# PressureSensorCircuit.net
KiCad netlist of a schematic drawn in Altium Designer
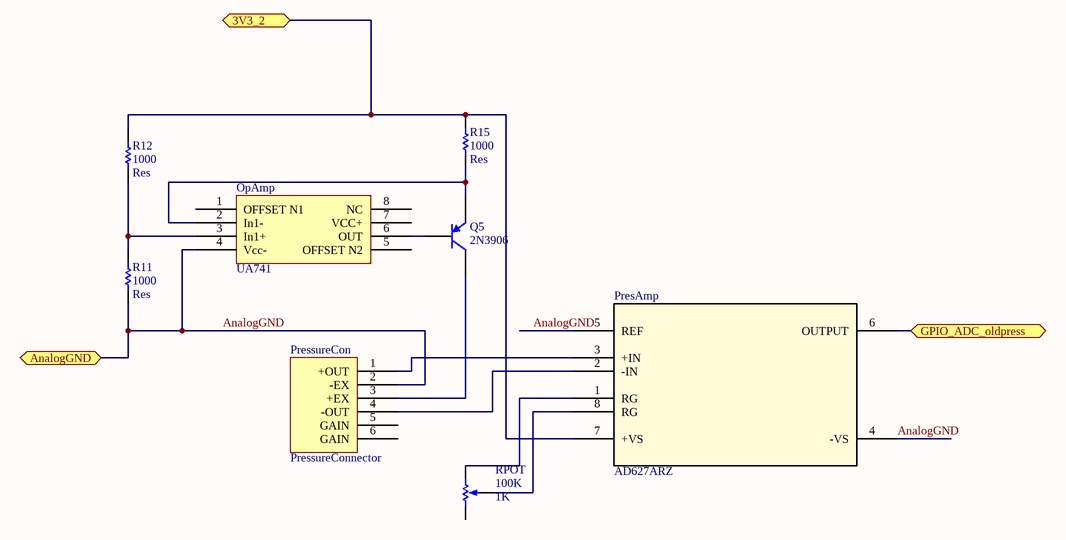
[diagram p0: PressureSensorCircuit.SchDoc]

(export (version "E")
  (design (tool "Eeschema 10.0.6"))
  (components
    (comp (ref "OpAmp")
      (value "UA741")
      (footprint "UmbilicalConnectors:UA741")
      (libsource (lib "UmbilicalBoardV2") (part "UA741"))
    )
    (comp (ref "PresAmp")
      (value "AD627ARZ")
      (footprint "R_8")
      (description "Imported")
      (libsource (lib "2016-04-06_02-20-10") (part "AD627ARZ"))
    )
    (comp (ref "PressureCon")
      (value "PressureConnector")
      (footprint "UmbilicalConnectors:Pressure Connector")
      (description "Molex 53261-0671")
      (libsource (lib "UmbilicalBoardV2") (part "PressureConnector"))
    )
    (comp (ref "Q5")
      (value "2N3906")
      (footprint "TO-92A")
      (description "PNP General Purpose Amplifier")
      (fields (field (name "PUBLISHER") "Altium Limited"))
      (libsource (lib "Miscellaneous Devices") (part "2N3906"))
    )
    (comp (ref "R11")
      (value "1000")
      (footprint "AXIAL-0.3")
      (description "Resistor- 696-1552-ND")
      (fields (field (name "ALTIUM_VALUE") "Res") (field (name "PUBLISHER") "Altium Limited"))
      (libsource (lib "Miscellaneous Devices") (part "Res1"))
    )
    (comp (ref "R12")
      (value "1000")
      (footprint "AXIAL-0.3")
      (description "Resistor- 696-1552-ND")
      (fields (field (name "ALTIUM_VALUE") "Res") (field (name "PUBLISHER") "Altium Limited"))
      (libsource (lib "Miscellaneous Devices") (part "Res1"))
    )
    (comp (ref "R15")
      (value "1000")
      (footprint "AXIAL-0.3")
      (description "Resistor- 696-1552-ND")
      (fields (field (name "ALTIUM_VALUE") "Res") (field (name "PUBLISHER") "Altium Limited"))
      (libsource (lib "Miscellaneous Devices") (part "Res1"))
    )
    (comp (ref "RPOT")
      (value "100K")
      (footprint "VR5")
      (description "Potentiometer")
      (fields (field (name "ALTIUM_VALUE") "1K") (field (name "PUBLISHER") "Altium Limited"))
      (libsource (lib "Miscellaneous Devices") (part "RPot"))
    )
  )
  (nets
    (net (code "1") (name "/3V3_2") (class "Default")
      (node (ref "PresAmp") (pin "7") (pinfunction "+VS_7") (pintype "passive"))
      (node (ref "R12") (pin "1") (pinfunction "1_1") (pintype "passive"))
      (node (ref "R15") (pin "1") (pinfunction "1_1") (pintype "passive"))
    )
    (net (code "2") (name "/AnalogGND") (class "Default")
      (node (ref "OpAmp") (pin "4") (pinfunction "Vcc-_4") (pintype "passive"))
      (node (ref "PresAmp") (pin "4") (pinfunction "-VS_4") (pintype "passive"))
      (node (ref "PresAmp") (pin "5") (pinfunction "REF_5") (pintype "passive"))
      (node (ref "PressureCon") (pin "2") (pinfunction "-EX_2") (pintype "passive"))
      (node (ref "R11") (pin "2") (pinfunction "2_2") (pintype "passive"))
    )
    (net (code "3") (name "/GPIO_ADC_oldpress") (class "Default")
      (node (ref "PresAmp") (pin "6") (pinfunction "OUTPUT_6") (pintype "passive"))
    )
    (net (code "4") (name "Net-(OpAmp-In1+)") (class "Default")
      (node (ref "OpAmp") (pin "3") (pinfunction "In1+_3") (pintype "passive"))
      (node (ref "R11") (pin "1") (pinfunction "1_1") (pintype "passive"))
      (node (ref "R12") (pin "2") (pinfunction "2_2") (pintype "passive"))
    )
    (net (code "5") (name "Net-(OpAmp-In1-)") (class "Default")
      (node (ref "OpAmp") (pin "2") (pinfunction "In1-_2") (pintype "passive"))
      (node (ref "Q5") (pin "1") (pinfunction "E_1") (pintype "passive"))
      (node (ref "R15") (pin "2") (pinfunction "2_2") (pintype "passive"))
    )
    (net (code "6") (name "Net-(OpAmp-OUT)") (class "Default")
      (node (ref "OpAmp") (pin "6") (pinfunction "OUT_6") (pintype "passive"))
      (node (ref "Q5") (pin "2") (pinfunction "B_2") (pintype "passive"))
    )
    (net (code "7") (name "Net-(PresAmp-+IN)") (class "Default")
      (node (ref "PresAmp") (pin "3") (pinfunction "+IN_3") (pintype "passive"))
      (node (ref "PressureCon") (pin "1") (pinfunction "+OUT_1") (pintype "passive"))
    )
    (net (code "8") (name "Net-(PresAmp--IN)") (class "Default")
      (node (ref "PresAmp") (pin "2") (pinfunction "-IN_2") (pintype "passive"))
      (node (ref "PressureCon") (pin "4") (pinfunction "-OUT_4") (pintype "passive"))
    )
    (net (code "9") (name "Net-(PressureCon-+EX)") (class "Default")
      (node (ref "PressureCon") (pin "3") (pinfunction "+EX_3") (pintype "passive"))
      (node (ref "Q5") (pin "3") (pinfunction "C_3") (pintype "passive"))
    )
    (net (code "10") (name "Net-(RPOT-BOT)") (class "Default")
      (node (ref "PresAmp") (pin "1") (pinfunction "RG_1") (pintype "passive"))
      (node (ref "RPOT") (pin "2") (pinfunction "BOT_2") (pintype "passive"))
    )
    (net (code "11") (name "Net-(RPOT-TAP)") (class "Default")
      (node (ref "PresAmp") (pin "8") (pinfunction "RG_8") (pintype "passive"))
      (node (ref "RPOT") (pin "3") (pinfunction "TAP_3") (pintype "passive"))
    )
    (net (code "12") (name "unconnected-(OpAmp-NC-Pad8)") (class "Default")
      (node (ref "OpAmp") (pin "8") (pinfunction "NC_8") (pintype "passive"))
    )
    (net (code "13") (name "unconnected-(OpAmp-OFFSET_N1-Pad1)") (class "Default")
      (node (ref "OpAmp") (pin "1") (pinfunction "OFFSET_N1_1") (pintype "passive"))
    )
    (net (code "14") (name "unconnected-(OpAmp-OFFSET_N2-Pad5)") (class "Default")
      (node (ref "OpAmp") (pin "5") (pinfunction "OFFSET_N2_5") (pintype "passive"))
    )
    (net (code "15") (name "unconnected-(OpAmp-VCC+-Pad7)") (class "Default")
      (node (ref "OpAmp") (pin "7") (pinfunction "VCC+_7") (pintype "passive"))
    )
    (net (code "16") (name "unconnected-(PressureCon-GAIN-Pad5)") (class "Default")
      (node (ref "PressureCon") (pin "5") (pinfunction "GAIN_5") (pintype "passive"))
    )
    (net (code "17") (name "unconnected-(PressureCon-GAIN-Pad6)") (class "Default")
      (node (ref "PressureCon") (pin "6") (pinfunction "GAIN_6") (pintype "passive"))
    )
    (net (code "18") (name "unconnected-(RPOT-TOP-Pad1)") (class "Default")
      (node (ref "RPOT") (pin "1") (pinfunction "TOP_1") (pintype "passive"))
    )
  )
)
